# dac-eval.net
KiCad netlist of a schematic drawn in EAGLE
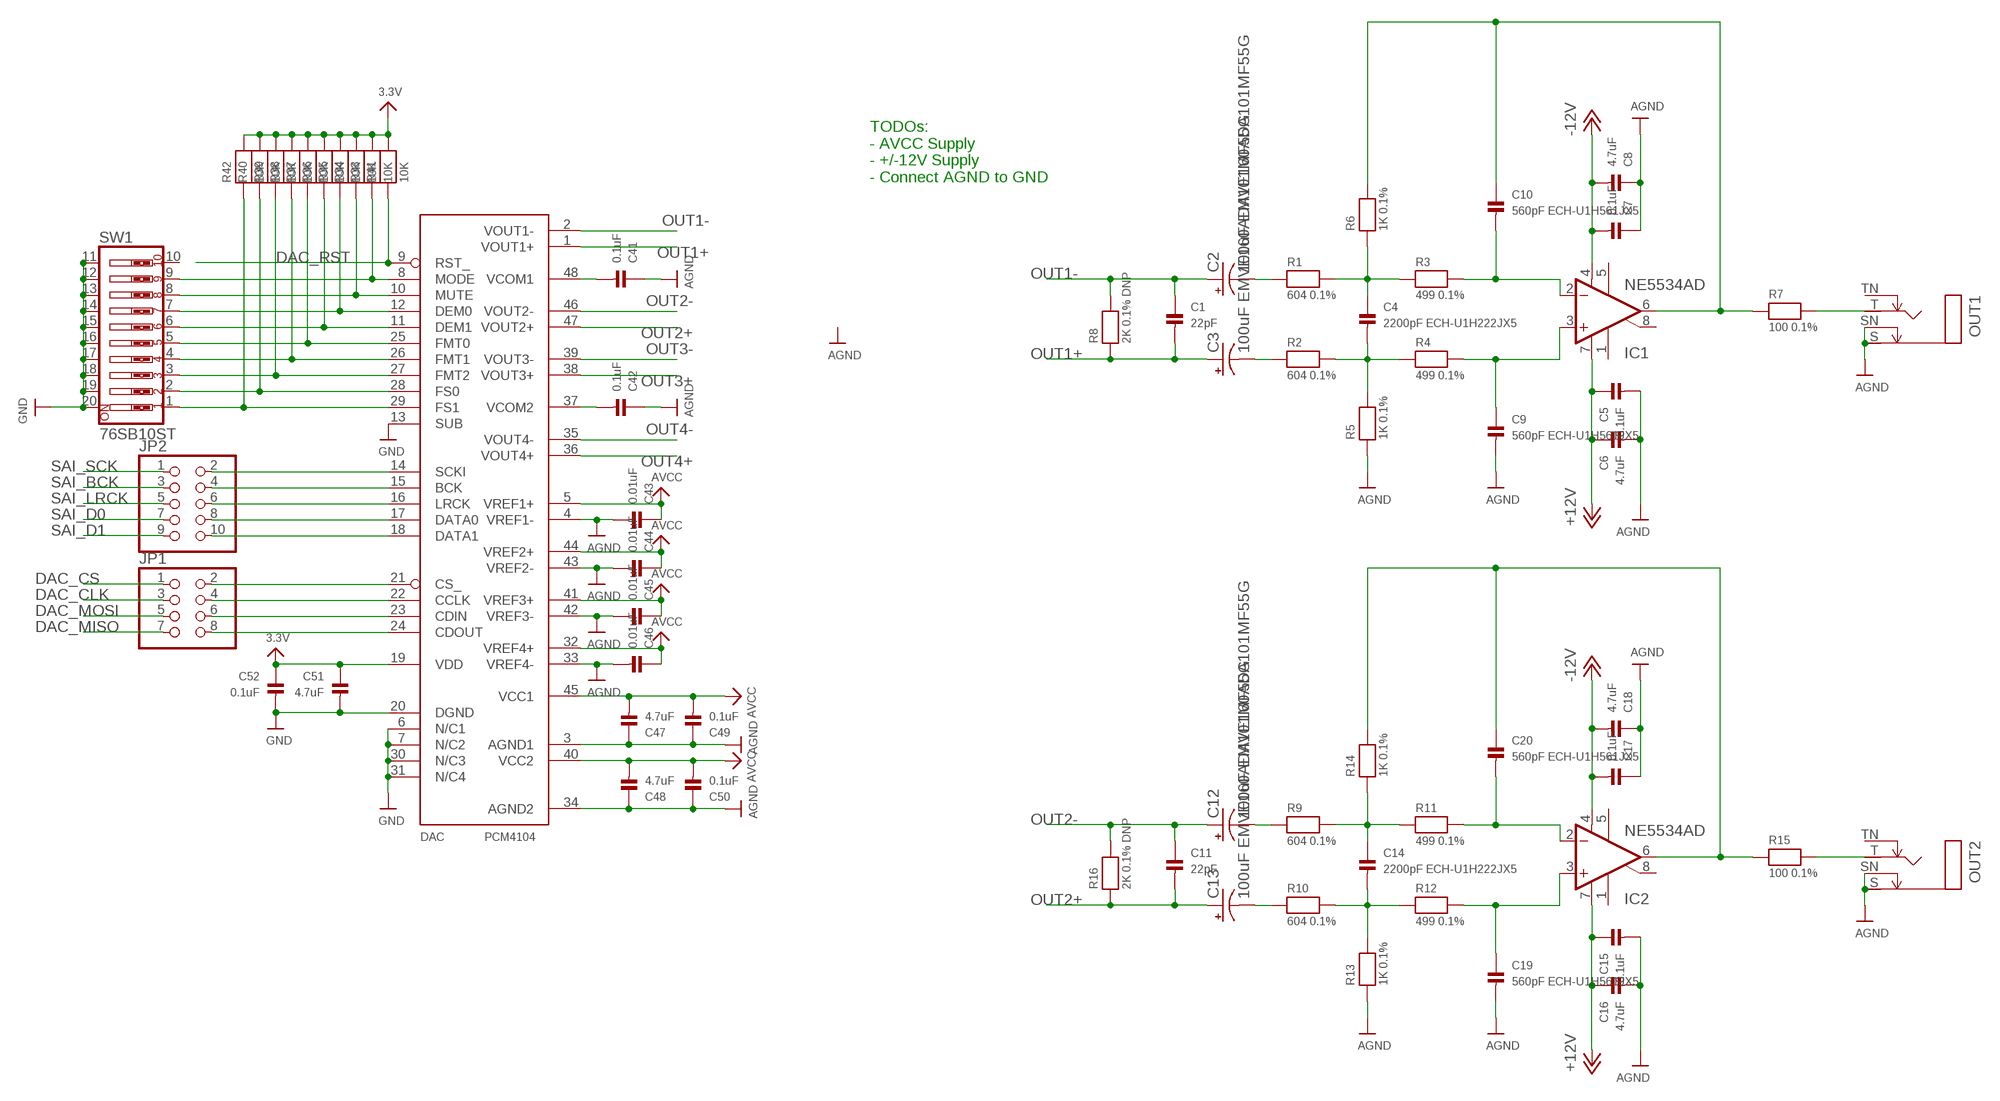
[diagram p0: schematic, sheet 1, part 1 of 2]
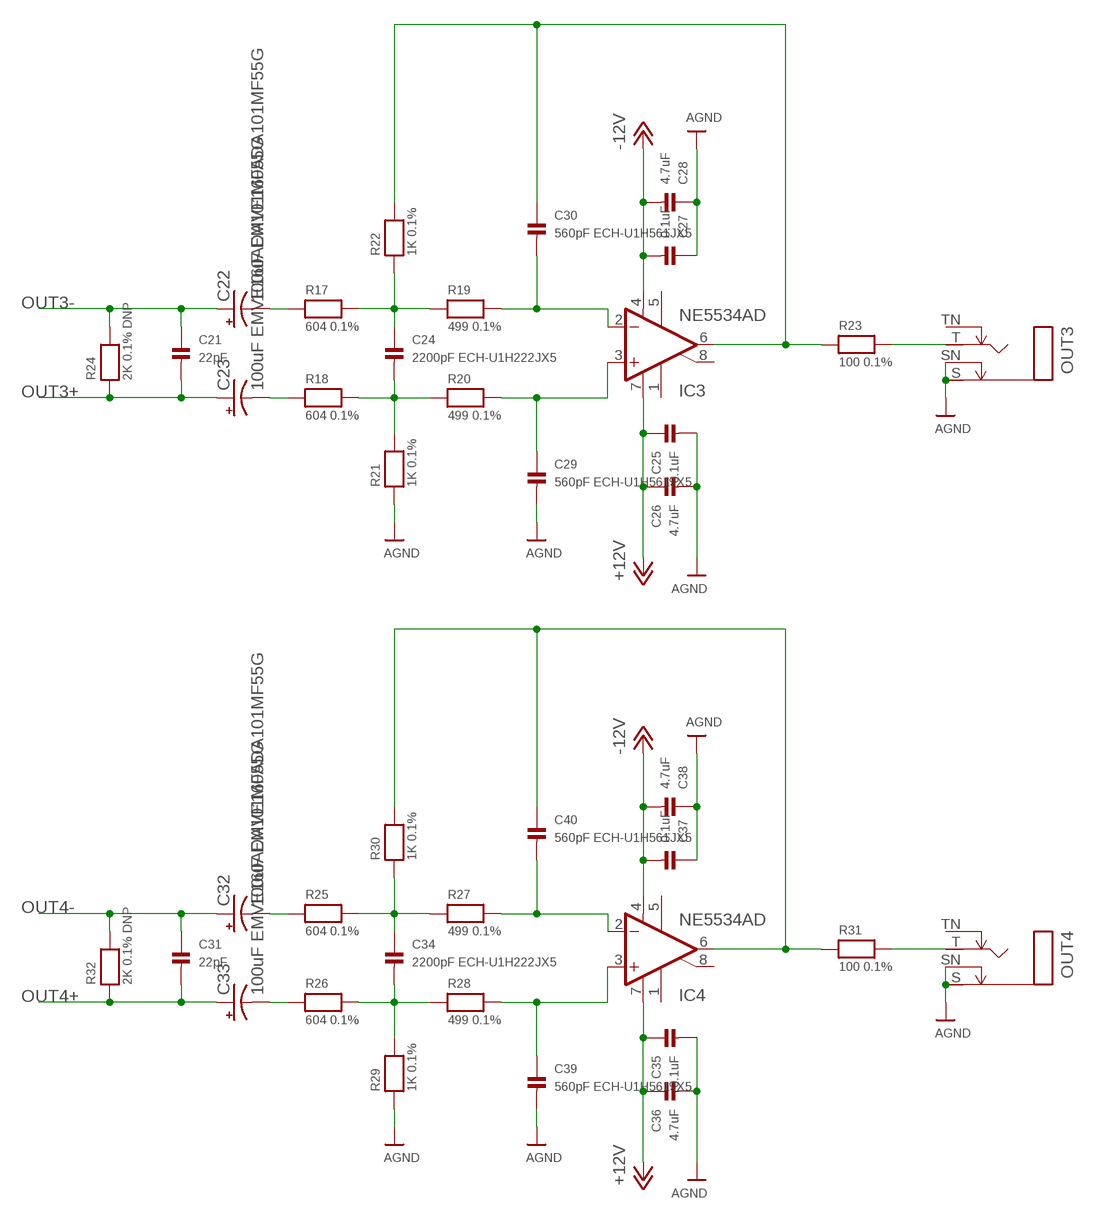
[diagram p1: schematic, sheet 1, part 2 of 2]

(export (version "E")
  (design (tool "Eeschema 10.0.6"))
  (components
    (comp (ref "C1")
      (value "22pF")
      (footprint "eagle-import:0603")
      (libsource (lib "eagle-import") (part "CAP_CERAMIC0603"))
    )
    (comp (ref "C2")
      (value "100uF EMVE160ADA101MF55G")
      (footprint "eagle-import:PANASONIC_D")
      (libsource (lib "eagle-import") (part "CAP_POLD"))
    )
    (comp (ref "C3")
      (value "100uF EMVE160ADA101MF55G")
      (footprint "eagle-import:PANASONIC_D")
      (libsource (lib "eagle-import") (part "CAP_POLD"))
    )
    (comp (ref "C4")
      (value "2200pF ECH-U1H222JX5")
      (footprint "eagle-import:0805")
      (libsource (lib "eagle-import") (part "CAP_CERAMIC0805"))
    )
    (comp (ref "C5")
      (value "0.1uF")
      (footprint "eagle-import:0603")
      (libsource (lib "eagle-import") (part "CAP_CERAMIC0603"))
    )
    (comp (ref "C6")
      (value "4.7uF")
      (footprint "eagle-import:0603")
      (libsource (lib "eagle-import") (part "CAP_CERAMIC0603"))
    )
    (comp (ref "C7")
      (value "0.1uF")
      (footprint "eagle-import:0603")
      (libsource (lib "eagle-import") (part "CAP_CERAMIC0603"))
    )
    (comp (ref "C8")
      (value "4.7uF")
      (footprint "eagle-import:0603")
      (libsource (lib "eagle-import") (part "CAP_CERAMIC0603"))
    )
    (comp (ref "C9")
      (value "560pF ECH-U1H561JX5")
      (footprint "eagle-import:0805")
      (libsource (lib "eagle-import") (part "CAP_CERAMIC0805"))
    )
    (comp (ref "C10")
      (value "560pF ECH-U1H561JX5")
      (footprint "eagle-import:0805")
      (libsource (lib "eagle-import") (part "CAP_CERAMIC0805"))
    )
    (comp (ref "C11")
      (value "22pF")
      (footprint "eagle-import:0603")
      (libsource (lib "eagle-import") (part "CAP_CERAMIC0603"))
    )
    (comp (ref "C12")
      (value "100uF EMVE160ADA101MF55G")
      (footprint "eagle-import:PANASONIC_D")
      (libsource (lib "eagle-import") (part "CAP_POLD"))
    )
    (comp (ref "C13")
      (value "100uF EMVE160ADA101MF55G")
      (footprint "eagle-import:PANASONIC_D")
      (libsource (lib "eagle-import") (part "CAP_POLD"))
    )
    (comp (ref "C14")
      (value "2200pF ECH-U1H222JX5")
      (footprint "eagle-import:0805")
      (libsource (lib "eagle-import") (part "CAP_CERAMIC0805"))
    )
    (comp (ref "C15")
      (value "0.1uF")
      (footprint "eagle-import:0603")
      (libsource (lib "eagle-import") (part "CAP_CERAMIC0603"))
    )
    (comp (ref "C16")
      (value "4.7uF")
      (footprint "eagle-import:0603")
      (libsource (lib "eagle-import") (part "CAP_CERAMIC0603"))
    )
    (comp (ref "C17")
      (value "0.1uF")
      (footprint "eagle-import:0603")
      (libsource (lib "eagle-import") (part "CAP_CERAMIC0603"))
    )
    (comp (ref "C18")
      (value "4.7uF")
      (footprint "eagle-import:0603")
      (libsource (lib "eagle-import") (part "CAP_CERAMIC0603"))
    )
    (comp (ref "C19")
      (value "560pF ECH-U1H561JX5")
      (footprint "eagle-import:0805")
      (libsource (lib "eagle-import") (part "CAP_CERAMIC0805"))
    )
    (comp (ref "C20")
      (value "560pF ECH-U1H561JX5")
      (footprint "eagle-import:0805")
      (libsource (lib "eagle-import") (part "CAP_CERAMIC0805"))
    )
    (comp (ref "C21")
      (value "22pF")
      (footprint "eagle-import:0603")
      (libsource (lib "eagle-import") (part "CAP_CERAMIC0603"))
    )
    (comp (ref "C22")
      (value "100uF EMVE160ADA101MF55G")
      (footprint "eagle-import:PANASONIC_D")
      (libsource (lib "eagle-import") (part "CAP_POLD"))
    )
    (comp (ref "C23")
      (value "100uF EMVE160ADA101MF55G")
      (footprint "eagle-import:PANASONIC_D")
      (libsource (lib "eagle-import") (part "CAP_POLD"))
    )
    (comp (ref "C24")
      (value "2200pF ECH-U1H222JX5")
      (footprint "eagle-import:0805")
      (libsource (lib "eagle-import") (part "CAP_CERAMIC0805"))
    )
    (comp (ref "C25")
      (value "0.1uF")
      (footprint "eagle-import:0603")
      (libsource (lib "eagle-import") (part "CAP_CERAMIC0603"))
    )
    (comp (ref "C26")
      (value "4.7uF")
      (footprint "eagle-import:0603")
      (libsource (lib "eagle-import") (part "CAP_CERAMIC0603"))
    )
    (comp (ref "C27")
      (value "0.1uF")
      (footprint "eagle-import:0603")
      (libsource (lib "eagle-import") (part "CAP_CERAMIC0603"))
    )
    (comp (ref "C28")
      (value "4.7uF")
      (footprint "eagle-import:0603")
      (libsource (lib "eagle-import") (part "CAP_CERAMIC0603"))
    )
    (comp (ref "C29")
      (value "560pF ECH-U1H561JX5")
      (footprint "eagle-import:0805")
      (libsource (lib "eagle-import") (part "CAP_CERAMIC0805"))
    )
    (comp (ref "C30")
      (value "560pF ECH-U1H561JX5")
      (footprint "eagle-import:0805")
      (libsource (lib "eagle-import") (part "CAP_CERAMIC0805"))
    )
    (comp (ref "C31")
      (value "22pF")
      (footprint "eagle-import:0603")
      (libsource (lib "eagle-import") (part "CAP_CERAMIC0603"))
    )
    (comp (ref "C32")
      (value "100uF EMVE160ADA101MF55G")
      (footprint "eagle-import:PANASONIC_D")
      (libsource (lib "eagle-import") (part "CAP_POLD"))
    )
    (comp (ref "C33")
      (value "100uF EMVE160ADA101MF55G")
      (footprint "eagle-import:PANASONIC_D")
      (libsource (lib "eagle-import") (part "CAP_POLD"))
    )
    (comp (ref "C34")
      (value "2200pF ECH-U1H222JX5")
      (footprint "eagle-import:0805")
      (libsource (lib "eagle-import") (part "CAP_CERAMIC0805"))
    )
    (comp (ref "C35")
      (value "0.1uF")
      (footprint "eagle-import:0603")
      (libsource (lib "eagle-import") (part "CAP_CERAMIC0603"))
    )
    (comp (ref "C36")
      (value "4.7uF")
      (footprint "eagle-import:0603")
      (libsource (lib "eagle-import") (part "CAP_CERAMIC0603"))
    )
    (comp (ref "C37")
      (value "0.1uF")
      (footprint "eagle-import:0603")
      (libsource (lib "eagle-import") (part "CAP_CERAMIC0603"))
    )
    (comp (ref "C38")
      (value "4.7uF")
      (footprint "eagle-import:0603")
      (libsource (lib "eagle-import") (part "CAP_CERAMIC0603"))
    )
    (comp (ref "C39")
      (value "560pF ECH-U1H561JX5")
      (footprint "eagle-import:0805")
      (libsource (lib "eagle-import") (part "CAP_CERAMIC0805"))
    )
    (comp (ref "C40")
      (value "560pF ECH-U1H561JX5")
      (footprint "eagle-import:0805")
      (libsource (lib "eagle-import") (part "CAP_CERAMIC0805"))
    )
    (comp (ref "C41")
      (value "0.1uF")
      (footprint "eagle-import:0603")
      (libsource (lib "eagle-import") (part "CAP_CERAMIC0603"))
    )
    (comp (ref "C42")
      (value "0.1uF")
      (footprint "eagle-import:0603")
      (libsource (lib "eagle-import") (part "CAP_CERAMIC0603"))
    )
    (comp (ref "C43")
      (value "0.01uF")
      (footprint "eagle-import:0603")
      (libsource (lib "eagle-import") (part "CAP_CERAMIC0603"))
    )
    (comp (ref "C44")
      (value "0.01uF")
      (footprint "eagle-import:0603")
      (libsource (lib "eagle-import") (part "CAP_CERAMIC0603"))
    )
    (comp (ref "C45")
      (value "0.01uF")
      (footprint "eagle-import:0603")
      (libsource (lib "eagle-import") (part "CAP_CERAMIC0603"))
    )
    (comp (ref "C46")
      (value "0.01uF")
      (footprint "eagle-import:0603")
      (libsource (lib "eagle-import") (part "CAP_CERAMIC0603"))
    )
    (comp (ref "C47")
      (value "4.7uF")
      (footprint "eagle-import:0603")
      (libsource (lib "eagle-import") (part "CAP_CERAMIC0603"))
    )
    (comp (ref "C48")
      (value "4.7uF")
      (footprint "eagle-import:0603")
      (libsource (lib "eagle-import") (part "CAP_CERAMIC0603"))
    )
    (comp (ref "C49")
      (value "0.1uF")
      (footprint "eagle-import:0603")
      (libsource (lib "eagle-import") (part "CAP_CERAMIC0603"))
    )
    (comp (ref "C50")
      (value "0.1uF")
      (footprint "eagle-import:0603")
      (libsource (lib "eagle-import") (part "CAP_CERAMIC0603"))
    )
    (comp (ref "C51")
      (value "4.7uF")
      (footprint "eagle-import:0603")
      (libsource (lib "eagle-import") (part "CAP_CERAMIC0603"))
    )
    (comp (ref "C52")
      (value "0.1uF")
      (footprint "eagle-import:0603")
      (libsource (lib "eagle-import") (part "CAP_CERAMIC0603"))
    )
    (comp (ref "DAC")
      (value "PCM4104")
      (footprint "eagle-import:SQFP-S-7X7-48")
      (libsource (lib "eagle-import") (part "PCM4104"))
    )
    (comp (ref "IC1")
      (value "NE5534AD")
      (footprint "eagle-import:SO08")
      (libsource (lib "eagle-import") (part "NE5534DA"))
    )
    (comp (ref "IC2")
      (value "NE5534AD")
      (footprint "eagle-import:SO08")
      (libsource (lib "eagle-import") (part "NE5534DA"))
    )
    (comp (ref "IC3")
      (value "NE5534AD")
      (footprint "eagle-import:SO08")
      (libsource (lib "eagle-import") (part "NE5534DA"))
    )
    (comp (ref "IC4")
      (value "NE5534AD")
      (footprint "eagle-import:SO08")
      (libsource (lib "eagle-import") (part "NE5534DA"))
    )
    (comp (ref "JP1")
      (value "PINHD-2X4")
      (footprint "eagle-import:2X04")
      (libsource (lib "eagle-import") (part "PINHD-2X4"))
    )
    (comp (ref "JP2")
      (value "PINHD-2X5")
      (footprint "eagle-import:2X05")
      (libsource (lib "eagle-import") (part "PINHD-2X5"))
    )
    (comp (ref "OUT1")
      (value "NMJ4HFD2")
      (footprint "eagle-import:NMJ4HC-S")
      (libsource (lib "eagle-import") (part "MONOSWS"))
    )
    (comp (ref "OUT2")
      (value "NMJ4HFD2")
      (footprint "eagle-import:NMJ4HC-S")
      (libsource (lib "eagle-import") (part "MONOSWS"))
    )
    (comp (ref "OUT3")
      (value "NMJ4HFD2")
      (footprint "eagle-import:NMJ4HC-S")
      (libsource (lib "eagle-import") (part "MONOSWS"))
    )
    (comp (ref "OUT4")
      (value "NMJ4HFD2")
      (footprint "eagle-import:NMJ4HC-S")
      (libsource (lib "eagle-import") (part "MONOSWS"))
    )
    (comp (ref "R1")
      (value "604 0.1%")
      (footprint "eagle-import:0603")
      (libsource (lib "eagle-import") (part "RESISTOR0603"))
    )
    (comp (ref "R2")
      (value "604 0.1%")
      (footprint "eagle-import:0603")
      (libsource (lib "eagle-import") (part "RESISTOR0603"))
    )
    (comp (ref "R3")
      (value "499 0.1%")
      (footprint "eagle-import:0603")
      (libsource (lib "eagle-import") (part "RESISTOR0603"))
    )
    (comp (ref "R4")
      (value "499 0.1%")
      (footprint "eagle-import:0603")
      (libsource (lib "eagle-import") (part "RESISTOR0603"))
    )
    (comp (ref "R5")
      (value "1K 0.1%")
      (footprint "eagle-import:0603")
      (libsource (lib "eagle-import") (part "RESISTOR0603"))
    )
    (comp (ref "R6")
      (value "1K 0.1%")
      (footprint "eagle-import:0603")
      (libsource (lib "eagle-import") (part "RESISTOR0603"))
    )
    (comp (ref "R7")
      (value "100 0.1%")
      (footprint "eagle-import:0603")
      (libsource (lib "eagle-import") (part "RESISTOR0603"))
    )
    (comp (ref "R8")
      (value "2K 0.1% DNP")
      (footprint "eagle-import:0603")
      (libsource (lib "eagle-import") (part "RESISTOR0603"))
    )
    (comp (ref "R9")
      (value "604 0.1%")
      (footprint "eagle-import:0603")
      (libsource (lib "eagle-import") (part "RESISTOR0603"))
    )
    (comp (ref "R10")
      (value "604 0.1%")
      (footprint "eagle-import:0603")
      (libsource (lib "eagle-import") (part "RESISTOR0603"))
    )
    (comp (ref "R11")
      (value "499 0.1%")
      (footprint "eagle-import:0603")
      (libsource (lib "eagle-import") (part "RESISTOR0603"))
    )
    (comp (ref "R12")
      (value "499 0.1%")
      (footprint "eagle-import:0603")
      (libsource (lib "eagle-import") (part "RESISTOR0603"))
    )
    (comp (ref "R13")
      (value "1K 0.1%")
      (footprint "eagle-import:0603")
      (libsource (lib "eagle-import") (part "RESISTOR0603"))
    )
    (comp (ref "R14")
      (value "1K 0.1%")
      (footprint "eagle-import:0603")
      (libsource (lib "eagle-import") (part "RESISTOR0603"))
    )
    (comp (ref "R15")
      (value "100 0.1%")
      (footprint "eagle-import:0603")
      (libsource (lib "eagle-import") (part "RESISTOR0603"))
    )
    (comp (ref "R16")
      (value "2K 0.1% DNP")
      (footprint "eagle-import:0603")
      (libsource (lib "eagle-import") (part "RESISTOR0603"))
    )
    (comp (ref "R17")
      (value "604 0.1%")
      (footprint "eagle-import:0603")
      (libsource (lib "eagle-import") (part "RESISTOR0603"))
    )
    (comp (ref "R18")
      (value "604 0.1%")
      (footprint "eagle-import:0603")
      (libsource (lib "eagle-import") (part "RESISTOR0603"))
    )
    (comp (ref "R19")
      (value "499 0.1%")
      (footprint "eagle-import:0603")
      (libsource (lib "eagle-import") (part "RESISTOR0603"))
    )
    (comp (ref "R20")
      (value "499 0.1%")
      (footprint "eagle-import:0603")
      (libsource (lib "eagle-import") (part "RESISTOR0603"))
    )
    (comp (ref "R21")
      (value "1K 0.1%")
      (footprint "eagle-import:0603")
      (libsource (lib "eagle-import") (part "RESISTOR0603"))
    )
    (comp (ref "R22")
      (value "1K 0.1%")
      (footprint "eagle-import:0603")
      (libsource (lib "eagle-import") (part "RESISTOR0603"))
    )
    (comp (ref "R23")
      (value "100 0.1%")
      (footprint "eagle-import:0603")
      (libsource (lib "eagle-import") (part "RESISTOR0603"))
    )
    (comp (ref "R24")
      (value "2K 0.1% DNP")
      (footprint "eagle-import:0603")
      (libsource (lib "eagle-import") (part "RESISTOR0603"))
    )
    (comp (ref "R25")
      (value "604 0.1%")
      (footprint "eagle-import:0603")
      (libsource (lib "eagle-import") (part "RESISTOR0603"))
    )
    (comp (ref "R26")
      (value "604 0.1%")
      (footprint "eagle-import:0603")
      (libsource (lib "eagle-import") (part "RESISTOR0603"))
    )
    (comp (ref "R27")
      (value "499 0.1%")
      (footprint "eagle-import:0603")
      (libsource (lib "eagle-import") (part "RESISTOR0603"))
    )
    (comp (ref "R28")
      (value "499 0.1%")
      (footprint "eagle-import:0603")
      (libsource (lib "eagle-import") (part "RESISTOR0603"))
    )
    (comp (ref "R29")
      (value "1K 0.1%")
      (footprint "eagle-import:0603")
      (libsource (lib "eagle-import") (part "RESISTOR0603"))
    )
    (comp (ref "R30")
      (value "1K 0.1%")
      (footprint "eagle-import:0603")
      (libsource (lib "eagle-import") (part "RESISTOR0603"))
    )
    (comp (ref "R31")
      (value "100 0.1%")
      (footprint "eagle-import:0603")
      (libsource (lib "eagle-import") (part "RESISTOR0603"))
    )
    (comp (ref "R32")
      (value "2K 0.1% DNP")
      (footprint "eagle-import:0603")
      (libsource (lib "eagle-import") (part "RESISTOR0603"))
    )
    (comp (ref "R33")
      (value "10K")
      (footprint "eagle-import:0603")
      (libsource (lib "eagle-import") (part "RESISTOR0603"))
    )
    (comp (ref "R34")
      (value "10K")
      (footprint "eagle-import:0603")
      (libsource (lib "eagle-import") (part "RESISTOR0603"))
    )
    (comp (ref "R35")
      (value "10K")
      (footprint "eagle-import:0603")
      (libsource (lib "eagle-import") (part "RESISTOR0603"))
    )
    (comp (ref "R36")
      (value "10K")
      (footprint "eagle-import:0603")
      (libsource (lib "eagle-import") (part "RESISTOR0603"))
    )
    (comp (ref "R37")
      (value "10K")
      (footprint "eagle-import:0603")
      (libsource (lib "eagle-import") (part "RESISTOR0603"))
    )
    (comp (ref "R38")
      (value "10K")
      (footprint "eagle-import:0603")
      (libsource (lib "eagle-import") (part "RESISTOR0603"))
    )
    (comp (ref "R39")
      (value "10K")
      (footprint "eagle-import:0603")
      (libsource (lib "eagle-import") (part "RESISTOR0603"))
    )
    (comp (ref "R40")
      (value "10K")
      (footprint "eagle-import:0603")
      (libsource (lib "eagle-import") (part "RESISTOR0603"))
    )
    (comp (ref "R41")
      (value "10K")
      (footprint "eagle-import:0603")
      (libsource (lib "eagle-import") (part "RESISTOR0603"))
    )
    (comp (ref "R42")
      (value "10K")
      (footprint "eagle-import:0603")
      (libsource (lib "eagle-import") (part "RESISTOR0603"))
    )
    (comp (ref "SW1")
      (value "76SB10ST")
      (footprint "eagle-import:EDG-10")
      (libsource (lib "eagle-import") (part "SW_DIP-10"))
    )
  )
  (nets
    (net (code "1") (name "+12V") (class "Default")
      (node (ref "C15") (pin "1") (pinfunction "P$1_1") (pintype "passive"))
      (node (ref "C16") (pin "1") (pinfunction "P$1_1") (pintype "passive"))
      (node (ref "C25") (pin "1") (pinfunction "P$1_1") (pintype "passive"))
      (node (ref "C26") (pin "1") (pinfunction "P$1_1") (pintype "passive"))
      (node (ref "C35") (pin "1") (pinfunction "P$1_1") (pintype "passive"))
      (node (ref "C36") (pin "1") (pinfunction "P$1_1") (pintype "passive"))
      (node (ref "C5") (pin "1") (pinfunction "P$1_1") (pintype "passive"))
      (node (ref "C6") (pin "1") (pinfunction "P$1_1") (pintype "passive"))
      (node (ref "IC1") (pin "7") (pinfunction "V+_7") (pintype "power_in"))
      (node (ref "IC2") (pin "7") (pinfunction "V+_7") (pintype "power_in"))
      (node (ref "IC3") (pin "7") (pinfunction "V+_7") (pintype "power_in"))
      (node (ref "IC4") (pin "7") (pinfunction "V+_7") (pintype "power_in"))
    )
    (net (code "2") (name "-12V") (class "Default")
      (node (ref "C17") (pin "2") (pinfunction "P$2_2") (pintype "passive"))
      (node (ref "C18") (pin "2") (pinfunction "P$2_2") (pintype "passive"))
      (node (ref "C27") (pin "2") (pinfunction "P$2_2") (pintype "passive"))
      (node (ref "C28") (pin "2") (pinfunction "P$2_2") (pintype "passive"))
      (node (ref "C37") (pin "2") (pinfunction "P$2_2") (pintype "passive"))
      (node (ref "C38") (pin "2") (pinfunction "P$2_2") (pintype "passive"))
      (node (ref "C7") (pin "2") (pinfunction "P$2_2") (pintype "passive"))
      (node (ref "C8") (pin "2") (pinfunction "P$2_2") (pintype "passive"))
      (node (ref "IC1") (pin "4") (pinfunction "V-_4") (pintype "power_in"))
      (node (ref "IC2") (pin "4") (pinfunction "V-_4") (pintype "power_in"))
      (node (ref "IC3") (pin "4") (pinfunction "V-_4") (pintype "power_in"))
      (node (ref "IC4") (pin "4") (pinfunction "V-_4") (pintype "power_in"))
    )
    (net (code "3") (name "/DAC_CLK") (class "Default")
      (node (ref "JP1") (pin "3") (pinfunction "3_3") (pintype "passive"))
    )
    (net (code "4") (name "/DAC_CS") (class "Default")
      (node (ref "JP1") (pin "1") (pinfunction "1_1") (pintype "passive"))
    )
    (net (code "5") (name "/DAC_MISO") (class "Default")
      (node (ref "JP1") (pin "7") (pinfunction "7_7") (pintype "passive"))
    )
    (net (code "6") (name "/DAC_MOSI") (class "Default")
      (node (ref "JP1") (pin "5") (pinfunction "5_5") (pintype "passive"))
    )
    (net (code "7") (name "/DAC_RST") (class "Default")
      (node (ref "DAC") (pin "9") (pinfunction "RST__9") (pintype "input"))
      (node (ref "R41") (pin "1") (pinfunction "1_1") (pintype "passive"))
    )
    (net (code "8") (name "/OUT1+") (class "Default")
      (node (ref "C1") (pin "2") (pinfunction "P$2_2") (pintype "passive"))
      (node (ref "C3") (pin "+") (pinfunction "+_+") (pintype "passive"))
      (node (ref "DAC") (pin "1") (pinfunction "VOUT1+_1") (pintype "output"))
      (node (ref "R8") (pin "1") (pinfunction "1_1") (pintype "passive"))
    )
    (net (code "9") (name "/OUT1-") (class "Default")
      (node (ref "C1") (pin "1") (pinfunction "P$1_1") (pintype "passive"))
      (node (ref "C2") (pin "+") (pinfunction "+_+") (pintype "passive"))
      (node (ref "DAC") (pin "2") (pinfunction "VOUT1-_2") (pintype "output"))
      (node (ref "R8") (pin "2") (pinfunction "2_2") (pintype "passive"))
    )
    (net (code "10") (name "/OUT2+") (class "Default")
      (node (ref "C11") (pin "2") (pinfunction "P$2_2") (pintype "passive"))
      (node (ref "C13") (pin "+") (pinfunction "+_+") (pintype "passive"))
      (node (ref "DAC") (pin "47") (pinfunction "VOUT2+_47") (pintype "output"))
      (node (ref "R16") (pin "1") (pinfunction "1_1") (pintype "passive"))
    )
    (net (code "11") (name "/OUT2-") (class "Default")
      (node (ref "C11") (pin "1") (pinfunction "P$1_1") (pintype "passive"))
      (node (ref "C12") (pin "+") (pinfunction "+_+") (pintype "passive"))
      (node (ref "DAC") (pin "46") (pinfunction "VOUT2-_46") (pintype "output"))
      (node (ref "R16") (pin "2") (pinfunction "2_2") (pintype "passive"))
    )
    (net (code "12") (name "/OUT3+") (class "Default")
      (node (ref "C21") (pin "2") (pinfunction "P$2_2") (pintype "passive"))
      (node (ref "C23") (pin "+") (pinfunction "+_+") (pintype "passive"))
      (node (ref "DAC") (pin "38") (pinfunction "VOUT3+_38") (pintype "output"))
      (node (ref "R24") (pin "1") (pinfunction "1_1") (pintype "passive"))
    )
    (net (code "13") (name "/OUT3-") (class "Default")
      (node (ref "C21") (pin "1") (pinfunction "P$1_1") (pintype "passive"))
      (node (ref "C22") (pin "+") (pinfunction "+_+") (pintype "passive"))
      (node (ref "DAC") (pin "39") (pinfunction "VOUT3-_39") (pintype "output"))
      (node (ref "R24") (pin "2") (pinfunction "2_2") (pintype "passive"))
    )
    (net (code "14") (name "/OUT4+") (class "Default")
      (node (ref "C31") (pin "2") (pinfunction "P$2_2") (pintype "passive"))
      (node (ref "C33") (pin "+") (pinfunction "+_+") (pintype "passive"))
      (node (ref "DAC") (pin "36") (pinfunction "VOUT4+_36") (pintype "output"))
      (node (ref "R32") (pin "1") (pinfunction "1_1") (pintype "passive"))
    )
    (net (code "15") (name "/OUT4-") (class "Default")
      (node (ref "C31") (pin "1") (pinfunction "P$1_1") (pintype "passive"))
      (node (ref "C32") (pin "+") (pinfunction "+_+") (pintype "passive"))
      (node (ref "DAC") (pin "35") (pinfunction "VOUT4-_35") (pintype "output"))
      (node (ref "R32") (pin "2") (pinfunction "2_2") (pintype "passive"))
    )
    (net (code "16") (name "/SAI_BCK") (class "Default")
      (node (ref "JP2") (pin "3") (pinfunction "3_3") (pintype "passive"))
    )
    (net (code "17") (name "/SAI_D0") (class "Default")
      (node (ref "JP2") (pin "7") (pinfunction "7_7") (pintype "passive"))
    )
    (net (code "18") (name "/SAI_D1") (class "Default")
      (node (ref "JP2") (pin "9") (pinfunction "9_9") (pintype "passive"))
    )
    (net (code "19") (name "/SAI_LRCK") (class "Default")
      (node (ref "JP2") (pin "5") (pinfunction "5_5") (pintype "passive"))
    )
    (net (code "20") (name "/SAI_SCK") (class "Default")
      (node (ref "JP2") (pin "1") (pinfunction "1_1") (pintype "passive"))
    )
    (net (code "21") (name "3.3V") (class "Default")
      (node (ref "C51") (pin "1") (pinfunction "P$1_1") (pintype "passive"))
      (node (ref "C52") (pin "1") (pinfunction "P$1_1") (pintype "passive"))
      (node (ref "DAC") (pin "19") (pinfunction "VDD_19") (pintype "power_in"))
      (node (ref "R33") (pin "2") (pinfunction "2_2") (pintype "passive"))
      (node (ref "R34") (pin "2") (pinfunction "2_2") (pintype "passive"))
      (node (ref "R35") (pin "2") (pinfunction "2_2") (pintype "passive"))
      (node (ref "R36") (pin "2") (pinfunction "2_2") (pintype "passive"))
      (node (ref "R37") (pin "2") (pinfunction "2_2") (pintype "passive"))
      (node (ref "R38") (pin "2") (pinfunction "2_2") (pintype "passive"))
      (node (ref "R39") (pin "2") (pinfunction "2_2") (pintype "passive"))
      (node (ref "R40") (pin "2") (pinfunction "2_2") (pintype "passive"))
      (node (ref "R41") (pin "2") (pinfunction "2_2") (pintype "passive"))
      (node (ref "R42") (pin "2") (pinfunction "2_2") (pintype "passive"))
    )
    (net (code "22") (name "AGND") (class "Default")
      (node (ref "C15") (pin "2") (pinfunction "P$2_2") (pintype "passive"))
      (node (ref "C16") (pin "2") (pinfunction "P$2_2") (pintype "passive"))
      (node (ref "C17") (pin "1") (pinfunction "P$1_1") (pintype "passive"))
      (node (ref "C18") (pin "1") (pinfunction "P$1_1") (pintype "passive"))
      (node (ref "C19") (pin "2") (pinfunction "P$2_2") (pintype "passive"))
      (node (ref "C25") (pin "2") (pinfunction "P$2_2") (pintype "passive"))
      (node (ref "C26") (pin "2") (pinfunction "P$2_2") (pintype "passive"))
      (node (ref "C27") (pin "1") (pinfunction "P$1_1") (pintype "passive"))
      (node (ref "C28") (pin "1") (pinfunction "P$1_1") (pintype "passive"))
      (node (ref "C29") (pin "2") (pinfunction "P$2_2") (pintype "passive"))
      (node (ref "C35") (pin "2") (pinfunction "P$2_2") (pintype "passive"))
      (node (ref "C36") (pin "2") (pinfunction "P$2_2") (pintype "passive"))
      (node (ref "C37") (pin "1") (pinfunction "P$1_1") (pintype "passive"))
      (node (ref "C38") (pin "1") (pinfunction "P$1_1") (pintype "passive"))
      (node (ref "C39") (pin "2") (pinfunction "P$2_2") (pintype "passive"))
      (node (ref "C41") (pin "1") (pinfunction "P$1_1") (pintype "passive"))
      (node (ref "C42") (pin "1") (pinfunction "P$1_1") (pintype "passive"))
      (node (ref "C43") (pin "2") (pinfunction "P$2_2") (pintype "passive"))
      (node (ref "C44") (pin "2") (pinfunction "P$2_2") (pintype "passive"))
      (node (ref "C45") (pin "2") (pinfunction "P$2_2") (pintype "passive"))
      (node (ref "C46") (pin "2") (pinfunction "P$2_2") (pintype "passive"))
      (node (ref "C47") (pin "1") (pinfunction "P$1_1") (pintype "passive"))
      (node (ref "C48") (pin "1") (pinfunction "P$1_1") (pintype "passive"))
      (node (ref "C49") (pin "1") (pinfunction "P$1_1") (pintype "passive"))
      (node (ref "C5") (pin "2") (pinfunction "P$2_2") (pintype "passive"))
      (node (ref "C50") (pin "1") (pinfunction "P$1_1") (pintype "passive"))
      (node (ref "C6") (pin "2") (pinfunction "P$2_2") (pintype "passive"))
      (node (ref "C7") (pin "1") (pinfunction "P$1_1") (pintype "passive"))
      (node (ref "C8") (pin "1") (pinfunction "P$1_1") (pintype "passive"))
      (node (ref "C9") (pin "2") (pinfunction "P$2_2") (pintype "passive"))
      (node (ref "DAC") (pin "3") (pinfunction "AGND1_3") (pintype "bidirectional"))
      (node (ref "DAC") (pin "33") (pinfunction "VREF4-_33") (pintype "input"))
      (node (ref "DAC") (pin "34") (pinfunction "AGND2_34") (pintype "bidirectional"))
      (node (ref "DAC") (pin "4") (pinfunction "VREF1-_4") (pintype "input"))
      (node (ref "DAC") (pin "42") (pinfunction "VREF3-_42") (pintype "bidirectional"))
      (node (ref "DAC") (pin "43") (pinfunction "VREF2-_43") (pintype "bidirectional"))
      (node (ref "OUT1") (pin "S") (pinfunction "S_S") (pintype "passive"))
      (node (ref "OUT1") (pin "SN") (pinfunction "SN_SN") (pintype "passive"))
      (node (ref "OUT2") (pin "S") (pinfunction "S_S") (pintype "passive"))
      (node (ref "OUT2") (pin "SN") (pinfunction "SN_SN") (pintype "passive"))
      (node (ref "OUT3") (pin "S") (pinfunction "S_S") (pintype "passive"))
      (node (ref "OUT3") (pin "SN") (pinfunction "SN_SN") (pintype "passive"))
      (node (ref "OUT4") (pin "S") (pinfunction "S_S") (pintype "passive"))
      (node (ref "OUT4") (pin "SN") (pinfunction "SN_SN") (pintype "passive"))
      (node (ref "R13") (pin "1") (pinfunction "1_1") (pintype "passive"))
      (node (ref "R21") (pin "1") (pinfunction "1_1") (pintype "passive"))
      (node (ref "R29") (pin "1") (pinfunction "1_1") (pintype "passive"))
      (node (ref "R5") (pin "1") (pinfunction "1_1") (pintype "passive"))
    )
    (net (code "23") (name "AVCC") (class "Default")
      (node (ref "C43") (pin "1") (pinfunction "P$1_1") (pintype "passive"))
      (node (ref "C44") (pin "1") (pinfunction "P$1_1") (pintype "passive"))
      (node (ref "C45") (pin "1") (pinfunction "P$1_1") (pintype "passive"))
      (node (ref "C46") (pin "1") (pinfunction "P$1_1") (pintype "passive"))
      (node (ref "C47") (pin "2") (pinfunction "P$2_2") (pintype "passive"))
      (node (ref "C48") (pin "2") (pinfunction "P$2_2") (pintype "passive"))
      (node (ref "C49") (pin "2") (pinfunction "P$2_2") (pintype "passive"))
      (node (ref "C50") (pin "2") (pinfunction "P$2_2") (pintype "passive"))
      (node (ref "DAC") (pin "32") (pinfunction "VREF4+_32") (pintype "input"))
      (node (ref "DAC") (pin "40") (pinfunction "VCC2_40") (pintype "bidirectional"))
      (node (ref "DAC") (pin "41") (pinfunction "VREF3+_41") (pintype "bidirectional"))
      (node (ref "DAC") (pin "44") (pinfunction "VREF2+_44") (pintype "bidirectional"))
      (node (ref "DAC") (pin "45") (pinfunction "VCC1_45") (pintype "bidirectional"))
      (node (ref "DAC") (pin "5") (pinfunction "VREF1+_5") (pintype "input"))
    )
    (net (code "24") (name "GND") (class "Default")
      (node (ref "C51") (pin "2") (pinfunction "P$2_2") (pintype "passive"))
      (node (ref "C52") (pin "2") (pinfunction "P$2_2") (pintype "passive"))
      (node (ref "DAC") (pin "13") (pinfunction "SUB_13") (pintype "input"))
      (node (ref "DAC") (pin "20") (pinfunction "DGND_20") (pintype "bidirectional"))
      (node (ref "DAC") (pin "30") (pinfunction "N/C3_30") (pintype "bidirectional"))
      (node (ref "DAC") (pin "31") (pinfunction "N/C4_31") (pintype "bidirectional"))
      (node (ref "DAC") (pin "6") (pinfunction "N/C1_6") (pintype "bidirectional"))
      (node (ref "DAC") (pin "7") (pinfunction "N/C2_7") (pintype "bidirectional"))
      (node (ref "SW1") (pin "11") (pinfunction "11_11") (pintype "passive"))
      (node (ref "SW1") (pin "12") (pinfunction "12_12") (pintype "passive"))
      (node (ref "SW1") (pin "13") (pinfunction "13_13") (pintype "passive"))
      (node (ref "SW1") (pin "14") (pinfunction "14_14") (pintype "passive"))
      (node (ref "SW1") (pin "15") (pinfunction "15_15") (pintype "passive"))
      (node (ref "SW1") (pin "16") (pinfunction "16_16") (pintype "passive"))
      (node (ref "SW1") (pin "17") (pinfunction "17_17") (pintype "passive"))
      (node (ref "SW1") (pin "18") (pinfunction "18_18") (pintype "passive"))
      (node (ref "SW1") (pin "19") (pinfunction "19_19") (pintype "passive"))
      (node (ref "SW1") (pin "20") (pinfunction "20_20") (pintype "passive"))
    )
    (net (code "25") (name "Net-(C2-Pad-)") (class "Default")
      (node (ref "C2") (pin "-") (pinfunction "-_-") (pintype "passive"))
      (node (ref "R1") (pin "1") (pinfunction "1_1") (pintype "passive"))
    )
    (net (code "26") (name "Net-(C3-Pad-)") (class "Default")
      (node (ref "C3") (pin "-") (pinfunction "-_-") (pintype "passive"))
      (node (ref "R2") (pin "1") (pinfunction "1_1") (pintype "passive"))
    )
    (net (code "27") (name "Net-(C4-P$1)") (class "Default")
      (node (ref "C4") (pin "1") (pinfunction "P$1_1") (pintype "passive"))
      (node (ref "R1") (pin "2") (pinfunction "2_2") (pintype "passive"))
      (node (ref "R3") (pin "1") (pinfunction "1_1") (pintype "passive"))
      (node (ref "R6") (pin "1") (pinfunction "1_1") (pintype "passive"))
    )
    (net (code "28") (name "Net-(C4-P$2)") (class "Default")
      (node (ref "C4") (pin "2") (pinfunction "P$2_2") (pintype "passive"))
      (node (ref "R2") (pin "2") (pinfunction "2_2") (pintype "passive"))
      (node (ref "R4") (pin "1") (pinfunction "1_1") (pintype "passive"))
      (node (ref "R5") (pin "2") (pinfunction "2_2") (pintype "passive"))
    )
    (net (code "29") (name "Net-(C9-P$1)") (class "Default")
      (node (ref "C9") (pin "1") (pinfunction "P$1_1") (pintype "passive"))
      (node (ref "IC1") (pin "3") (pinfunction "+IN_3") (pintype "input"))
      (node (ref "R4") (pin "2") (pinfunction "2_2") (pintype "passive"))
    )
    (net (code "30") (name "Net-(C10-P$1)") (class "Default")
      (node (ref "C10") (pin "1") (pinfunction "P$1_1") (pintype "passive"))
      (node (ref "IC1") (pin "6") (pinfunction "OUT_6") (pintype "output"))
      (node (ref "R6") (pin "2") (pinfunction "2_2") (pintype "passive"))
      (node (ref "R7") (pin "1") (pinfunction "1_1") (pintype "passive"))
    )
    (net (code "31") (name "Net-(C10-P$2)") (class "Default")
      (node (ref "C10") (pin "2") (pinfunction "P$2_2") (pintype "passive"))
      (node (ref "IC1") (pin "2") (pinfunction "-IN_2") (pintype "input"))
      (node (ref "R3") (pin "2") (pinfunction "2_2") (pintype "passive"))
    )
    (net (code "32") (name "Net-(C12-Pad-)") (class "Default")
      (node (ref "C12") (pin "-") (pinfunction "-_-") (pintype "passive"))
      (node (ref "R9") (pin "1") (pinfunction "1_1") (pintype "passive"))
    )
    (net (code "33") (name "Net-(C13-Pad-)") (class "Default")
      (node (ref "C13") (pin "-") (pinfunction "-_-") (pintype "passive"))
      (node (ref "R10") (pin "1") (pinfunction "1_1") (pintype "passive"))
    )
    (net (code "34") (name "Net-(C14-P$1)") (class "Default")
      (node (ref "C14") (pin "1") (pinfunction "P$1_1") (pintype "passive"))
      (node (ref "R11") (pin "1") (pinfunction "1_1") (pintype "passive"))
      (node (ref "R14") (pin "1") (pinfunction "1_1") (pintype "passive"))
      (node (ref "R9") (pin "2") (pinfunction "2_2") (pintype "passive"))
    )
    (net (code "35") (name "Net-(C14-P$2)") (class "Default")
      (node (ref "C14") (pin "2") (pinfunction "P$2_2") (pintype "passive"))
      (node (ref "R10") (pin "2") (pinfunction "2_2") (pintype "passive"))
      (node (ref "R12") (pin "1") (pinfunction "1_1") (pintype "passive"))
      (node (ref "R13") (pin "2") (pinfunction "2_2") (pintype "passive"))
    )
    (net (code "36") (name "Net-(C19-P$1)") (class "Default")
      (node (ref "C19") (pin "1") (pinfunction "P$1_1") (pintype "passive"))
      (node (ref "IC2") (pin "3") (pinfunction "+IN_3") (pintype "input"))
      (node (ref "R12") (pin "2") (pinfunction "2_2") (pintype "passive"))
    )
    (net (code "37") (name "Net-(C20-P$1)") (class "Default")
      (node (ref "C20") (pin "1") (pinfunction "P$1_1") (pintype "passive"))
      (node (ref "IC2") (pin "6") (pinfunction "OUT_6") (pintype "output"))
      (node (ref "R14") (pin "2") (pinfunction "2_2") (pintype "passive"))
      (node (ref "R15") (pin "1") (pinfunction "1_1") (pintype "passive"))
    )
    (net (code "38") (name "Net-(C20-P$2)") (class "Default")
      (node (ref "C20") (pin "2") (pinfunction "P$2_2") (pintype "passive"))
      (node (ref "IC2") (pin "2") (pinfunction "-IN_2") (pintype "input"))
      (node (ref "R11") (pin "2") (pinfunction "2_2") (pintype "passive"))
    )
    (net (code "39") (name "Net-(C22-Pad-)") (class "Default")
      (node (ref "C22") (pin "-") (pinfunction "-_-") (pintype "passive"))
      (node (ref "R17") (pin "1") (pinfunction "1_1") (pintype "passive"))
    )
    (net (code "40") (name "Net-(C23-Pad-)") (class "Default")
      (node (ref "C23") (pin "-") (pinfunction "-_-") (pintype "passive"))
      (node (ref "R18") (pin "1") (pinfunction "1_1") (pintype "passive"))
    )
    (net (code "41") (name "Net-(C24-P$1)") (class "Default")
      (node (ref "C24") (pin "1") (pinfunction "P$1_1") (pintype "passive"))
      (node (ref "R17") (pin "2") (pinfunction "2_2") (pintype "passive"))
      (node (ref "R19") (pin "1") (pinfunction "1_1") (pintype "passive"))
      (node (ref "R22") (pin "1") (pinfunction "1_1") (pintype "passive"))
    )
    (net (code "42") (name "Net-(C24-P$2)") (class "Default")
      (node (ref "C24") (pin "2") (pinfunction "P$2_2") (pintype "passive"))
      (node (ref "R18") (pin "2") (pinfunction "2_2") (pintype "passive"))
      (node (ref "R20") (pin "1") (pinfunction "1_1") (pintype "passive"))
      (node (ref "R21") (pin "2") (pinfunction "2_2") (pintype "passive"))
    )
    (net (code "43") (name "Net-(C29-P$1)") (class "Default")
      (node (ref "C29") (pin "1") (pinfunction "P$1_1") (pintype "passive"))
      (node (ref "IC3") (pin "3") (pinfunction "+IN_3") (pintype "input"))
      (node (ref "R20") (pin "2") (pinfunction "2_2") (pintype "passive"))
    )
    (net (code "44") (name "Net-(C30-P$1)") (class "Default")
      (node (ref "C30") (pin "1") (pinfunction "P$1_1") (pintype "passive"))
      (node (ref "IC3") (pin "6") (pinfunction "OUT_6") (pintype "output"))
      (node (ref "R22") (pin "2") (pinfunction "2_2") (pintype "passive"))
      (node (ref "R23") (pin "1") (pinfunction "1_1") (pintype "passive"))
    )
    (net (code "45") (name "Net-(C30-P$2)") (class "Default")
      (node (ref "C30") (pin "2") (pinfunction "P$2_2") (pintype "passive"))
      (node (ref "IC3") (pin "2") (pinfunction "-IN_2") (pintype "input"))
      (node (ref "R19") (pin "2") (pinfunction "2_2") (pintype "passive"))
    )
    (net (code "46") (name "Net-(C32-Pad-)") (class "Default")
      (node (ref "C32") (pin "-") (pinfunction "-_-") (pintype "passive"))
      (node (ref "R25") (pin "1") (pinfunction "1_1") (pintype "passive"))
    )
    (net (code "47") (name "Net-(C33-Pad-)") (class "Default")
      (node (ref "C33") (pin "-") (pinfunction "-_-") (pintype "passive"))
      (node (ref "R26") (pin "1") (pinfunction "1_1") (pintype "passive"))
    )
    (net (code "48") (name "Net-(C34-P$1)") (class "Default")
      (node (ref "C34") (pin "1") (pinfunction "P$1_1") (pintype "passive"))
      (node (ref "R25") (pin "2") (pinfunction "2_2") (pintype "passive"))
      (node (ref "R27") (pin "1") (pinfunction "1_1") (pintype "passive"))
      (node (ref "R30") (pin "1") (pinfunction "1_1") (pintype "passive"))
    )
    (net (code "49") (name "Net-(C34-P$2)") (class "Default")
      (node (ref "C34") (pin "2") (pinfunction "P$2_2") (pintype "passive"))
      (node (ref "R26") (pin "2") (pinfunction "2_2") (pintype "passive"))
      (node (ref "R28") (pin "1") (pinfunction "1_1") (pintype "passive"))
      (node (ref "R29") (pin "2") (pinfunction "2_2") (pintype "passive"))
    )
    (net (code "50") (name "Net-(C39-P$1)") (class "Default")
      (node (ref "C39") (pin "1") (pinfunction "P$1_1") (pintype "passive"))
      (node (ref "IC4") (pin "3") (pinfunction "+IN_3") (pintype "input"))
      (node (ref "R28") (pin "2") (pinfunction "2_2") (pintype "passive"))
    )
    (net (code "51") (name "Net-(C40-P$1)") (class "Default")
      (node (ref "C40") (pin "1") (pinfunction "P$1_1") (pintype "passive"))
      (node (ref "IC4") (pin "6") (pinfunction "OUT_6") (pintype "output"))
      (node (ref "R30") (pin "2") (pinfunction "2_2") (pintype "passive"))
      (node (ref "R31") (pin "1") (pinfunction "1_1") (pintype "passive"))
    )
    (net (code "52") (name "Net-(C40-P$2)") (class "Default")
      (node (ref "C40") (pin "2") (pinfunction "P$2_2") (pintype "passive"))
      (node (ref "IC4") (pin "2") (pinfunction "-IN_2") (pintype "input"))
      (node (ref "R27") (pin "2") (pinfunction "2_2") (pintype "passive"))
    )
    (net (code "53") (name "Net-(C41-P$2)") (class "Default")
      (node (ref "C41") (pin "2") (pinfunction "P$2_2") (pintype "passive"))
      (node (ref "DAC") (pin "48") (pinfunction "VCOM1_48") (pintype "output"))
    )
    (net (code "54") (name "Net-(C42-P$2)") (class "Default")
      (node (ref "C42") (pin "2") (pinfunction "P$2_2") (pintype "passive"))
      (node (ref "DAC") (pin "37") (pinfunction "VCOM2_37") (pintype "output"))
    )
    (net (code "55") (name "Net-(DAC-BCK)") (class "Default")
      (node (ref "DAC") (pin "15") (pinfunction "BCK_15") (pintype "input"))
      (node (ref "JP2") (pin "4") (pinfunction "4_4") (pintype "passive"))
    )
    (net (code "56") (name "Net-(DAC-CCLK)") (class "Default")
      (node (ref "DAC") (pin "22") (pinfunction "CCLK_22") (pintype "input"))
      (node (ref "JP1") (pin "4") (pinfunction "4_4") (pintype "passive"))
    )
    (net (code "57") (name "Net-(DAC-CDIN)") (class "Default")
      (node (ref "DAC") (pin "23") (pinfunction "CDIN_23") (pintype "input"))
      (node (ref "JP1") (pin "6") (pinfunction "6_6") (pintype "passive"))
    )
    (net (code "58") (name "Net-(DAC-CDOUT)") (class "Default")
      (node (ref "DAC") (pin "24") (pinfunction "CDOUT_24") (pintype "output"))
      (node (ref "JP1") (pin "8") (pinfunction "8_8") (pintype "passive"))
    )
    (net (code "59") (name "Net-(DAC-CS_)") (class "Default")
      (node (ref "DAC") (pin "21") (pinfunction "CS__21") (pintype "input"))
      (node (ref "JP1") (pin "2") (pinfunction "2_2") (pintype "passive"))
    )
    (net (code "60") (name "Net-(DAC-DATA0)") (class "Default")
      (node (ref "DAC") (pin "17") (pinfunction "DATA0_17") (pintype "input"))
      (node (ref "JP2") (pin "8") (pinfunction "8_8") (pintype "passive"))
    )
    (net (code "61") (name "Net-(DAC-DATA1)") (class "Default")
      (node (ref "DAC") (pin "18") (pinfunction "DATA1_18") (pintype "input"))
      (node (ref "JP2") (pin "10") (pinfunction "10_10") (pintype "passive"))
    )
    (net (code "62") (name "Net-(DAC-DEM0)") (class "Default")
      (node (ref "DAC") (pin "12") (pinfunction "DEM0_12") (pintype "input"))
      (node (ref "R35") (pin "1") (pinfunction "1_1") (pintype "passive"))
      (node (ref "SW1") (pin "7") (pinfunction "7_7") (pintype "passive"))
    )
    (net (code "63") (name "Net-(DAC-DEM1)") (class "Default")
      (node (ref "DAC") (pin "11") (pinfunction "DEM1_11") (pintype "input"))
      (node (ref "R36") (pin "1") (pinfunction "1_1") (pintype "passive"))
      (node (ref "SW1") (pin "6") (pinfunction "6_6") (pintype "passive"))
    )
    (net (code "64") (name "Net-(DAC-FMT0)") (class "Default")
      (node (ref "DAC") (pin "25") (pinfunction "FMT0_25") (pintype "input"))
      (node (ref "R37") (pin "1") (pinfunction "1_1") (pintype "passive"))
      (node (ref "SW1") (pin "5") (pinfunction "5_5") (pintype "passive"))
    )
    (net (code "65") (name "Net-(DAC-FMT1)") (class "Default")
      (node (ref "DAC") (pin "26") (pinfunction "FMT1_26") (pintype "input"))
      (node (ref "R38") (pin "1") (pinfunction "1_1") (pintype "passive"))
      (node (ref "SW1") (pin "4") (pinfunction "4_4") (pintype "passive"))
    )
    (net (code "66") (name "Net-(DAC-FMT2)") (class "Default")
      (node (ref "DAC") (pin "27") (pinfunction "FMT2_27") (pintype "input"))
      (node (ref "R39") (pin "1") (pinfunction "1_1") (pintype "passive"))
      (node (ref "SW1") (pin "3") (pinfunction "3_3") (pintype "passive"))
    )
    (net (code "67") (name "Net-(DAC-FS0)") (class "Default")
      (node (ref "DAC") (pin "28") (pinfunction "FS0_28") (pintype "input"))
      (node (ref "R40") (pin "1") (pinfunction "1_1") (pintype "passive"))
      (node (ref "SW1") (pin "2") (pinfunction "2_2") (pintype "passive"))
    )
    (net (code "68") (name "Net-(DAC-FS1)") (class "Default")
      (node (ref "DAC") (pin "29") (pinfunction "FS1_29") (pintype "input"))
      (node (ref "R42") (pin "1") (pinfunction "1_1") (pintype "passive"))
      (node (ref "SW1") (pin "1") (pinfunction "1_1") (pintype "passive"))
    )
    (net (code "69") (name "Net-(DAC-LRCK)") (class "Default")
      (node (ref "DAC") (pin "16") (pinfunction "LRCK_16") (pintype "input"))
      (node (ref "JP2") (pin "6") (pinfunction "6_6") (pintype "passive"))
    )
    (net (code "70") (name "Net-(DAC-MODE)") (class "Default")
      (node (ref "DAC") (pin "8") (pinfunction "MODE_8") (pintype "input"))
      (node (ref "R33") (pin "1") (pinfunction "1_1") (pintype "passive"))
      (node (ref "SW1") (pin "9") (pinfunction "9_9") (pintype "passive"))
    )
    (net (code "71") (name "Net-(DAC-MUTE)") (class "Default")
      (node (ref "DAC") (pin "10") (pinfunction "MUTE_10") (pintype "input"))
      (node (ref "R34") (pin "1") (pinfunction "1_1") (pintype "passive"))
      (node (ref "SW1") (pin "8") (pinfunction "8_8") (pintype "passive"))
    )
    (net (code "72") (name "Net-(DAC-SCKI)") (class "Default")
      (node (ref "DAC") (pin "14") (pinfunction "SCKI_14") (pintype "input"))
      (node (ref "JP2") (pin "2") (pinfunction "2_2") (pintype "passive"))
    )
    (net (code "73") (name "Net-(OUT1-PadT)") (class "Default")
      (node (ref "OUT1") (pin "T") (pinfunction "T_T") (pintype "passive"))
      (node (ref "R7") (pin "2") (pinfunction "2_2") (pintype "passive"))
    )
    (net (code "74") (name "Net-(OUT2-PadT)") (class "Default")
      (node (ref "OUT2") (pin "T") (pinfunction "T_T") (pintype "passive"))
      (node (ref "R15") (pin "2") (pinfunction "2_2") (pintype "passive"))
    )
    (net (code "75") (name "Net-(OUT3-PadT)") (class "Default")
      (node (ref "OUT3") (pin "T") (pinfunction "T_T") (pintype "passive"))
      (node (ref "R23") (pin "2") (pinfunction "2_2") (pintype "passive"))
    )
    (net (code "76") (name "Net-(OUT4-PadT)") (class "Default")
      (node (ref "OUT4") (pin "T") (pinfunction "T_T") (pintype "passive"))
      (node (ref "R31") (pin "2") (pinfunction "2_2") (pintype "passive"))
    )
    (net (code "77") (name "unconnected-(IC1-CMP-Pad5)") (class "Default")
      (node (ref "IC1") (pin "5") (pinfunction "CMP_5") (pintype "passive"))
    )
    (net (code "78") (name "unconnected-(IC1-ON-Pad1)") (class "Default")
      (node (ref "IC1") (pin "1") (pinfunction "ON_1") (pintype "passive"))
    )
    (net (code "79") (name "unconnected-(IC1-ON{slash}CMP-Pad8)") (class "Default")
      (node (ref "IC1") (pin "8") (pinfunction "ON/CMP_8") (pintype "passive"))
    )
    (net (code "80") (name "unconnected-(IC2-CMP-Pad5)") (class "Default")
      (node (ref "IC2") (pin "5") (pinfunction "CMP_5") (pintype "passive"))
    )
    (net (code "81") (name "unconnected-(IC2-ON-Pad1)") (class "Default")
      (node (ref "IC2") (pin "1") (pinfunction "ON_1") (pintype "passive"))
    )
    (net (code "82") (name "unconnected-(IC2-ON{slash}CMP-Pad8)") (class "Default")
      (node (ref "IC2") (pin "8") (pinfunction "ON/CMP_8") (pintype "passive"))
    )
    (net (code "83") (name "unconnected-(IC3-CMP-Pad5)") (class "Default")
      (node (ref "IC3") (pin "5") (pinfunction "CMP_5") (pintype "passive"))
    )
    (net (code "84") (name "unconnected-(IC3-ON-Pad1)") (class "Default")
      (node (ref "IC3") (pin "1") (pinfunction "ON_1") (pintype "passive"))
    )
    (net (code "85") (name "unconnected-(IC3-ON{slash}CMP-Pad8)") (class "Default")
      (node (ref "IC3") (pin "8") (pinfunction "ON/CMP_8") (pintype "passive"))
    )
    (net (code "86") (name "unconnected-(IC4-CMP-Pad5)") (class "Default")
      (node (ref "IC4") (pin "5") (pinfunction "CMP_5") (pintype "passive"))
    )
    (net (code "87") (name "unconnected-(IC4-ON-Pad1)") (class "Default")
      (node (ref "IC4") (pin "1") (pinfunction "ON_1") (pintype "passive"))
    )
    (net (code "88") (name "unconnected-(IC4-ON{slash}CMP-Pad8)") (class "Default")
      (node (ref "IC4") (pin "8") (pinfunction "ON/CMP_8") (pintype "passive"))
    )
    (net (code "89") (name "unconnected-(OUT1-PadTN)") (class "Default")
      (node (ref "OUT1") (pin "TN") (pinfunction "TN_TN") (pintype "passive"))
    )
    (net (code "90") (name "unconnected-(OUT2-PadTN)") (class "Default")
      (node (ref "OUT2") (pin "TN") (pinfunction "TN_TN") (pintype "passive"))
    )
    (net (code "91") (name "unconnected-(OUT3-PadTN)") (class "Default")
      (node (ref "OUT3") (pin "TN") (pinfunction "TN_TN") (pintype "passive"))
    )
    (net (code "92") (name "unconnected-(OUT4-PadTN)") (class "Default")
      (node (ref "OUT4") (pin "TN") (pinfunction "TN_TN") (pintype "passive"))
    )
    (net (code "93") (name "unconnected-(SW1-Pad10)") (class "Default")
      (node (ref "SW1") (pin "10") (pinfunction "10_10") (pintype "passive"))
    )
  )
)
